# Clocl.net
KiCad netlist of a schematic drawn in Altium Designer
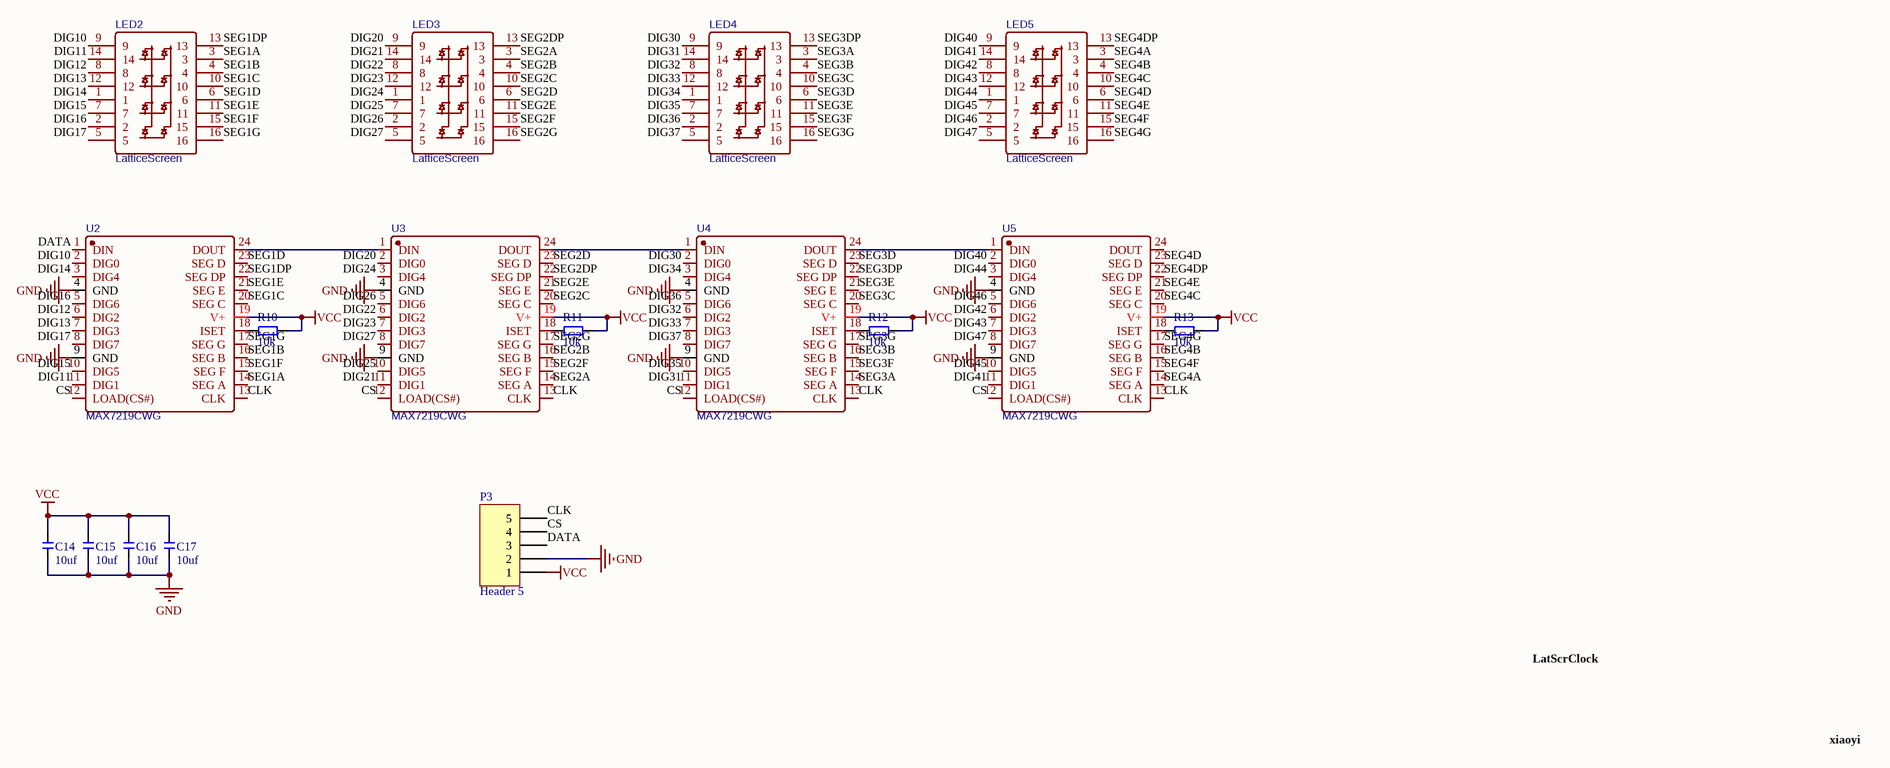
[diagram p0: Clocl.SchDoc]

(export (version "E")
  (design (tool "Eeschema 10.0.6"))
  (components
    (comp (ref "C14")
      (value "10uf")
      (footprint "C0805")
      (description "无极电容")
      (libsource (lib "SWJTUCar") (part "CAP"))
    )
    (comp (ref "C15")
      (value "10uf")
      (footprint "C0805")
      (description "无极电容")
      (libsource (lib "SWJTUCar") (part "CAP"))
    )
    (comp (ref "C16")
      (value "10uf")
      (footprint "C0805")
      (description "无极电容")
      (libsource (lib "SWJTUCar") (part "CAP"))
    )
    (comp (ref "C17")
      (value "10uf")
      (footprint "C0805")
      (description "无极电容")
      (libsource (lib "SWJTUCar") (part "CAP"))
    )
    (comp (ref "LED2")
      (value "LatticeScreen")
      (footprint "SLD1388DRA1GD_20_withheaders")
      (description "8*8共阴点阵屏")
      (fields
        (field (name "BOM_SUPPLIER PART") "C225991")
        (field (name "BOM_MANUFACTURER PART") "SLD1388DRA1GD")
        (field (name "CONTRIBUTOR") "LCSC")
      )
      (libsource (lib "myself") (part "LatticeScreen"))
    )
    (comp (ref "LED3")
      (value "LatticeScreen")
      (footprint "SLD1388DRA1GD_20_withheaders")
      (description "8*8共阴点阵屏")
      (fields
        (field (name "BOM_SUPPLIER PART") "C225991")
        (field (name "BOM_MANUFACTURER PART") "SLD1388DRA1GD")
        (field (name "CONTRIBUTOR") "LCSC")
      )
      (libsource (lib "myself") (part "LatticeScreen"))
    )
    (comp (ref "LED4")
      (value "LatticeScreen")
      (footprint "SLD1388DRA1GD_20_withheaders")
      (description "8*8共阴点阵屏")
      (fields
        (field (name "BOM_SUPPLIER PART") "C225991")
        (field (name "BOM_MANUFACTURER PART") "SLD1388DRA1GD")
        (field (name "CONTRIBUTOR") "LCSC")
      )
      (libsource (lib "myself") (part "LatticeScreen"))
    )
    (comp (ref "LED5")
      (value "LatticeScreen")
      (footprint "SLD1388DRA1GD_20_withheaders")
      (description "8*8共阴点阵屏")
      (fields
        (field (name "BOM_SUPPLIER PART") "C225991")
        (field (name "BOM_MANUFACTURER PART") "SLD1388DRA1GD")
        (field (name "CONTRIBUTOR") "LCSC")
      )
      (libsource (lib "myself") (part "LatticeScreen"))
    )
    (comp (ref "P3")
      (value "Header 5")
      (footprint "HDR1X5")
      (description "Header, 5-Pin")
      (fields (field (name "PUBLISHER") "Altium Limited"))
      (libsource (lib "Miscellaneous Connectors") (part "Header 5"))
    )
    (comp (ref "R10")
      (value "10k")
      (footprint "R0805")
      (description "电阻")
      (libsource (lib "SWJTUCar") (part "RES"))
    )
    (comp (ref "R11")
      (value "10k")
      (footprint "R0805")
      (description "电阻")
      (libsource (lib "SWJTUCar") (part "RES"))
    )
    (comp (ref "R12")
      (value "10k")
      (footprint "R0805")
      (description "电阻")
      (libsource (lib "SWJTUCar") (part "RES"))
    )
    (comp (ref "R13")
      (value "10k")
      (footprint "R0805")
      (description "电阻")
      (libsource (lib "SWJTUCar") (part "RES"))
    )
    (comp (ref "U2")
      (value "MAX7219CWG")
      (footprint "SOP-24_L15.2-W7.8-P1.27-LS10.6-BL")
      (description "共阴极显示驱动")
      (fields (field (name "BOM_SUPPLIER PART") "C9964"))
      (libsource (lib "myself") (part "MAX7219CWG"))
    )
    (comp (ref "U3")
      (value "MAX7219CWG")
      (footprint "SOP-24_L15.2-W7.8-P1.27-LS10.6-BL")
      (description "共阴极显示驱动")
      (fields (field (name "BOM_SUPPLIER PART") "C9964"))
      (libsource (lib "myself") (part "MAX7219CWG"))
    )
    (comp (ref "U4")
      (value "MAX7219CWG")
      (footprint "SOP-24_L15.2-W7.8-P1.27-LS10.6-BL")
      (description "共阴极显示驱动")
      (fields (field (name "BOM_SUPPLIER PART") "C9964"))
      (libsource (lib "myself") (part "MAX7219CWG"))
    )
    (comp (ref "U5")
      (value "MAX7219CWG")
      (footprint "SOP-24_L15.2-W7.8-P1.27-LS10.6-BL")
      (description "共阴极显示驱动")
      (fields (field (name "BOM_SUPPLIER PART") "C9964"))
      (libsource (lib "myself") (part "MAX7219CWG"))
    )
  )
  (nets
    (net (code "1") (name "/CLK") (class "Default")
      (node (ref "P3") (pin "5") (pinfunction "5_5") (pintype "passive"))
      (node (ref "U2") (pin "13") (pinfunction "CLK_13") (pintype "passive"))
      (node (ref "U3") (pin "13") (pinfunction "CLK_13") (pintype "passive"))
      (node (ref "U4") (pin "13") (pinfunction "CLK_13") (pintype "passive"))
      (node (ref "U5") (pin "13") (pinfunction "CLK_13") (pintype "passive"))
    )
    (net (code "2") (name "/CS") (class "Default")
      (node (ref "P3") (pin "4") (pinfunction "4_4") (pintype "passive"))
      (node (ref "U2") (pin "12") (pinfunction "LOAD(CS#)_12") (pintype "passive"))
      (node (ref "U3") (pin "12") (pinfunction "LOAD(CS#)_12") (pintype "passive"))
      (node (ref "U4") (pin "12") (pinfunction "LOAD(CS#)_12") (pintype "passive"))
      (node (ref "U5") (pin "12") (pinfunction "LOAD(CS#)_12") (pintype "passive"))
    )
    (net (code "3") (name "/DATA") (class "Default")
      (node (ref "P3") (pin "3") (pinfunction "3_3") (pintype "passive"))
      (node (ref "U2") (pin "1") (pinfunction "DIN_1") (pintype "passive"))
    )
    (net (code "4") (name "/DIG10") (class "Default")
      (node (ref "LED2") (pin "9") (pinfunction "9_9") (pintype "passive"))
      (node (ref "U2") (pin "2") (pinfunction "DIG0_2") (pintype "passive"))
    )
    (net (code "5") (name "/DIG11") (class "Default")
      (node (ref "LED2") (pin "14") (pinfunction "14_14") (pintype "passive"))
      (node (ref "U2") (pin "11") (pinfunction "DIG1_11") (pintype "passive"))
    )
    (net (code "6") (name "/DIG12") (class "Default")
      (node (ref "LED2") (pin "8") (pinfunction "8_8") (pintype "passive"))
      (node (ref "U2") (pin "6") (pinfunction "DIG2_6") (pintype "passive"))
    )
    (net (code "7") (name "/DIG13") (class "Default")
      (node (ref "LED2") (pin "12") (pinfunction "12_12") (pintype "passive"))
      (node (ref "U2") (pin "7") (pinfunction "DIG3_7") (pintype "passive"))
    )
    (net (code "8") (name "/DIG14") (class "Default")
      (node (ref "LED2") (pin "1") (pinfunction "1_1") (pintype "passive"))
      (node (ref "U2") (pin "3") (pinfunction "DIG4_3") (pintype "passive"))
    )
    (net (code "9") (name "/DIG15") (class "Default")
      (node (ref "LED2") (pin "7") (pinfunction "7_7") (pintype "passive"))
      (node (ref "U2") (pin "10") (pinfunction "DIG5_10") (pintype "passive"))
    )
    (net (code "10") (name "/DIG16") (class "Default")
      (node (ref "LED2") (pin "2") (pinfunction "2_2") (pintype "passive"))
      (node (ref "U2") (pin "5") (pinfunction "DIG6_5") (pintype "passive"))
    )
    (net (code "11") (name "/DIG17") (class "Default")
      (node (ref "LED2") (pin "5") (pinfunction "5_5") (pintype "passive"))
      (node (ref "U2") (pin "8") (pinfunction "DIG7_8") (pintype "passive"))
    )
    (net (code "12") (name "/DIG20") (class "Default")
      (node (ref "LED3") (pin "9") (pinfunction "9_9") (pintype "passive"))
      (node (ref "U3") (pin "2") (pinfunction "DIG0_2") (pintype "passive"))
    )
    (net (code "13") (name "/DIG21") (class "Default")
      (node (ref "LED3") (pin "14") (pinfunction "14_14") (pintype "passive"))
      (node (ref "U3") (pin "11") (pinfunction "DIG1_11") (pintype "passive"))
    )
    (net (code "14") (name "/DIG22") (class "Default")
      (node (ref "LED3") (pin "8") (pinfunction "8_8") (pintype "passive"))
      (node (ref "U3") (pin "6") (pinfunction "DIG2_6") (pintype "passive"))
    )
    (net (code "15") (name "/DIG23") (class "Default")
      (node (ref "LED3") (pin "12") (pinfunction "12_12") (pintype "passive"))
      (node (ref "U3") (pin "7") (pinfunction "DIG3_7") (pintype "passive"))
    )
    (net (code "16") (name "/DIG24") (class "Default")
      (node (ref "LED3") (pin "1") (pinfunction "1_1") (pintype "passive"))
      (node (ref "U3") (pin "3") (pinfunction "DIG4_3") (pintype "passive"))
    )
    (net (code "17") (name "/DIG25") (class "Default")
      (node (ref "LED3") (pin "7") (pinfunction "7_7") (pintype "passive"))
      (node (ref "U3") (pin "10") (pinfunction "DIG5_10") (pintype "passive"))
    )
    (net (code "18") (name "/DIG26") (class "Default")
      (node (ref "LED3") (pin "2") (pinfunction "2_2") (pintype "passive"))
      (node (ref "U3") (pin "5") (pinfunction "DIG6_5") (pintype "passive"))
    )
    (net (code "19") (name "/DIG27") (class "Default")
      (node (ref "LED3") (pin "5") (pinfunction "5_5") (pintype "passive"))
      (node (ref "U3") (pin "8") (pinfunction "DIG7_8") (pintype "passive"))
    )
    (net (code "20") (name "/DIG30") (class "Default")
      (node (ref "LED4") (pin "9") (pinfunction "9_9") (pintype "passive"))
      (node (ref "U4") (pin "2") (pinfunction "DIG0_2") (pintype "passive"))
    )
    (net (code "21") (name "/DIG31") (class "Default")
      (node (ref "LED4") (pin "14") (pinfunction "14_14") (pintype "passive"))
      (node (ref "U4") (pin "11") (pinfunction "DIG1_11") (pintype "passive"))
    )
    (net (code "22") (name "/DIG32") (class "Default")
      (node (ref "LED4") (pin "8") (pinfunction "8_8") (pintype "passive"))
      (node (ref "U4") (pin "6") (pinfunction "DIG2_6") (pintype "passive"))
    )
    (net (code "23") (name "/DIG33") (class "Default")
      (node (ref "LED4") (pin "12") (pinfunction "12_12") (pintype "passive"))
      (node (ref "U4") (pin "7") (pinfunction "DIG3_7") (pintype "passive"))
    )
    (net (code "24") (name "/DIG34") (class "Default")
      (node (ref "LED4") (pin "1") (pinfunction "1_1") (pintype "passive"))
      (node (ref "U4") (pin "3") (pinfunction "DIG4_3") (pintype "passive"))
    )
    (net (code "25") (name "/DIG35") (class "Default")
      (node (ref "LED4") (pin "7") (pinfunction "7_7") (pintype "passive"))
      (node (ref "U4") (pin "10") (pinfunction "DIG5_10") (pintype "passive"))
    )
    (net (code "26") (name "/DIG36") (class "Default")
      (node (ref "LED4") (pin "2") (pinfunction "2_2") (pintype "passive"))
      (node (ref "U4") (pin "5") (pinfunction "DIG6_5") (pintype "passive"))
    )
    (net (code "27") (name "/DIG37") (class "Default")
      (node (ref "LED4") (pin "5") (pinfunction "5_5") (pintype "passive"))
      (node (ref "U4") (pin "8") (pinfunction "DIG7_8") (pintype "passive"))
    )
    (net (code "28") (name "/DIG40") (class "Default")
      (node (ref "LED5") (pin "9") (pinfunction "9_9") (pintype "passive"))
      (node (ref "U5") (pin "2") (pinfunction "DIG0_2") (pintype "passive"))
    )
    (net (code "29") (name "/DIG41") (class "Default")
      (node (ref "LED5") (pin "14") (pinfunction "14_14") (pintype "passive"))
      (node (ref "U5") (pin "11") (pinfunction "DIG1_11") (pintype "passive"))
    )
    (net (code "30") (name "/DIG42") (class "Default")
      (node (ref "LED5") (pin "8") (pinfunction "8_8") (pintype "passive"))
      (node (ref "U5") (pin "6") (pinfunction "DIG2_6") (pintype "passive"))
    )
    (net (code "31") (name "/DIG43") (class "Default")
      (node (ref "LED5") (pin "12") (pinfunction "12_12") (pintype "passive"))
      (node (ref "U5") (pin "7") (pinfunction "DIG3_7") (pintype "passive"))
    )
    (net (code "32") (name "/DIG44") (class "Default")
      (node (ref "LED5") (pin "1") (pinfunction "1_1") (pintype "passive"))
      (node (ref "U5") (pin "3") (pinfunction "DIG4_3") (pintype "passive"))
    )
    (net (code "33") (name "/DIG45") (class "Default")
      (node (ref "LED5") (pin "7") (pinfunction "7_7") (pintype "passive"))
      (node (ref "U5") (pin "10") (pinfunction "DIG5_10") (pintype "passive"))
    )
    (net (code "34") (name "/DIG46") (class "Default")
      (node (ref "LED5") (pin "2") (pinfunction "2_2") (pintype "passive"))
      (node (ref "U5") (pin "5") (pinfunction "DIG6_5") (pintype "passive"))
    )
    (net (code "35") (name "/DIG47") (class "Default")
      (node (ref "LED5") (pin "5") (pinfunction "5_5") (pintype "passive"))
      (node (ref "U5") (pin "8") (pinfunction "DIG7_8") (pintype "passive"))
    )
    (net (code "36") (name "/SEG1A") (class "Default")
      (node (ref "LED2") (pin "3") (pinfunction "3_3") (pintype "passive"))
      (node (ref "U2") (pin "14") (pinfunction "SEG_A_14") (pintype "passive"))
    )
    (net (code "37") (name "/SEG1B") (class "Default")
      (node (ref "LED2") (pin "4") (pinfunction "4_4") (pintype "passive"))
      (node (ref "U2") (pin "16") (pinfunction "SEG_B_16") (pintype "passive"))
    )
    (net (code "38") (name "/SEG1C") (class "Default")
      (node (ref "LED2") (pin "10") (pinfunction "10_10") (pintype "passive"))
      (node (ref "U2") (pin "20") (pinfunction "SEG_C_20") (pintype "passive"))
    )
    (net (code "39") (name "/SEG1D") (class "Default")
      (node (ref "LED2") (pin "6") (pinfunction "6_6") (pintype "passive"))
      (node (ref "U2") (pin "23") (pinfunction "SEG_D_23") (pintype "passive"))
    )
    (net (code "40") (name "/SEG1DP") (class "Default")
      (node (ref "LED2") (pin "13") (pinfunction "13_13") (pintype "passive"))
      (node (ref "U2") (pin "22") (pinfunction "SEG_DP_22") (pintype "passive"))
    )
    (net (code "41") (name "/SEG1E") (class "Default")
      (node (ref "LED2") (pin "11") (pinfunction "11_11") (pintype "passive"))
      (node (ref "U2") (pin "21") (pinfunction "SEG_E_21") (pintype "passive"))
    )
    (net (code "42") (name "/SEG1F") (class "Default")
      (node (ref "LED2") (pin "15") (pinfunction "15_15") (pintype "passive"))
      (node (ref "U2") (pin "15") (pinfunction "SEG_F_15") (pintype "passive"))
    )
    (net (code "43") (name "/SEG1G") (class "Default")
      (node (ref "LED2") (pin "16") (pinfunction "16_16") (pintype "passive"))
      (node (ref "U2") (pin "17") (pinfunction "SEG_G_17") (pintype "passive"))
    )
    (net (code "44") (name "/SEG2A") (class "Default")
      (node (ref "LED3") (pin "3") (pinfunction "3_3") (pintype "passive"))
      (node (ref "U3") (pin "14") (pinfunction "SEG_A_14") (pintype "passive"))
    )
    (net (code "45") (name "/SEG2B") (class "Default")
      (node (ref "LED3") (pin "4") (pinfunction "4_4") (pintype "passive"))
      (node (ref "U3") (pin "16") (pinfunction "SEG_B_16") (pintype "passive"))
    )
    (net (code "46") (name "/SEG2C") (class "Default")
      (node (ref "LED3") (pin "10") (pinfunction "10_10") (pintype "passive"))
      (node (ref "U3") (pin "20") (pinfunction "SEG_C_20") (pintype "passive"))
    )
    (net (code "47") (name "/SEG2D") (class "Default")
      (node (ref "LED3") (pin "6") (pinfunction "6_6") (pintype "passive"))
      (node (ref "U3") (pin "23") (pinfunction "SEG_D_23") (pintype "passive"))
    )
    (net (code "48") (name "/SEG2DP") (class "Default")
      (node (ref "LED3") (pin "13") (pinfunction "13_13") (pintype "passive"))
      (node (ref "U3") (pin "22") (pinfunction "SEG_DP_22") (pintype "passive"))
    )
    (net (code "49") (name "/SEG2E") (class "Default")
      (node (ref "LED3") (pin "11") (pinfunction "11_11") (pintype "passive"))
      (node (ref "U3") (pin "21") (pinfunction "SEG_E_21") (pintype "passive"))
    )
    (net (code "50") (name "/SEG2F") (class "Default")
      (node (ref "LED3") (pin "15") (pinfunction "15_15") (pintype "passive"))
      (node (ref "U3") (pin "15") (pinfunction "SEG_F_15") (pintype "passive"))
    )
    (net (code "51") (name "/SEG2G") (class "Default")
      (node (ref "LED3") (pin "16") (pinfunction "16_16") (pintype "passive"))
      (node (ref "U3") (pin "17") (pinfunction "SEG_G_17") (pintype "passive"))
    )
    (net (code "52") (name "/SEG3A") (class "Default")
      (node (ref "LED4") (pin "3") (pinfunction "3_3") (pintype "passive"))
      (node (ref "U4") (pin "14") (pinfunction "SEG_A_14") (pintype "passive"))
    )
    (net (code "53") (name "/SEG3B") (class "Default")
      (node (ref "LED4") (pin "4") (pinfunction "4_4") (pintype "passive"))
      (node (ref "U4") (pin "16") (pinfunction "SEG_B_16") (pintype "passive"))
    )
    (net (code "54") (name "/SEG3C") (class "Default")
      (node (ref "LED4") (pin "10") (pinfunction "10_10") (pintype "passive"))
      (node (ref "U4") (pin "20") (pinfunction "SEG_C_20") (pintype "passive"))
    )
    (net (code "55") (name "/SEG3D") (class "Default")
      (node (ref "LED4") (pin "6") (pinfunction "6_6") (pintype "passive"))
      (node (ref "U4") (pin "23") (pinfunction "SEG_D_23") (pintype "passive"))
    )
    (net (code "56") (name "/SEG3DP") (class "Default")
      (node (ref "LED4") (pin "13") (pinfunction "13_13") (pintype "passive"))
      (node (ref "U4") (pin "22") (pinfunction "SEG_DP_22") (pintype "passive"))
    )
    (net (code "57") (name "/SEG3E") (class "Default")
      (node (ref "LED4") (pin "11") (pinfunction "11_11") (pintype "passive"))
      (node (ref "U4") (pin "21") (pinfunction "SEG_E_21") (pintype "passive"))
    )
    (net (code "58") (name "/SEG3F") (class "Default")
      (node (ref "LED4") (pin "15") (pinfunction "15_15") (pintype "passive"))
      (node (ref "U4") (pin "15") (pinfunction "SEG_F_15") (pintype "passive"))
    )
    (net (code "59") (name "/SEG3G") (class "Default")
      (node (ref "LED4") (pin "16") (pinfunction "16_16") (pintype "passive"))
      (node (ref "U4") (pin "17") (pinfunction "SEG_G_17") (pintype "passive"))
    )
    (net (code "60") (name "/SEG4A") (class "Default")
      (node (ref "LED5") (pin "3") (pinfunction "3_3") (pintype "passive"))
      (node (ref "U5") (pin "14") (pinfunction "SEG_A_14") (pintype "passive"))
    )
    (net (code "61") (name "/SEG4B") (class "Default")
      (node (ref "LED5") (pin "4") (pinfunction "4_4") (pintype "passive"))
      (node (ref "U5") (pin "16") (pinfunction "SEG_B_16") (pintype "passive"))
    )
    (net (code "62") (name "/SEG4C") (class "Default")
      (node (ref "LED5") (pin "10") (pinfunction "10_10") (pintype "passive"))
      (node (ref "U5") (pin "20") (pinfunction "SEG_C_20") (pintype "passive"))
    )
    (net (code "63") (name "/SEG4D") (class "Default")
      (node (ref "LED5") (pin "6") (pinfunction "6_6") (pintype "passive"))
      (node (ref "U5") (pin "23") (pinfunction "SEG_D_23") (pintype "passive"))
    )
    (net (code "64") (name "/SEG4DP") (class "Default")
      (node (ref "LED5") (pin "13") (pinfunction "13_13") (pintype "passive"))
      (node (ref "U5") (pin "22") (pinfunction "SEG_DP_22") (pintype "passive"))
    )
    (net (code "65") (name "/SEG4E") (class "Default")
      (node (ref "LED5") (pin "11") (pinfunction "11_11") (pintype "passive"))
      (node (ref "U5") (pin "21") (pinfunction "SEG_E_21") (pintype "passive"))
    )
    (net (code "66") (name "/SEG4F") (class "Default")
      (node (ref "LED5") (pin "15") (pinfunction "15_15") (pintype "passive"))
      (node (ref "U5") (pin "15") (pinfunction "SEG_F_15") (pintype "passive"))
    )
    (net (code "67") (name "/SEG4G") (class "Default")
      (node (ref "LED5") (pin "16") (pinfunction "16_16") (pintype "passive"))
      (node (ref "U5") (pin "17") (pinfunction "SEG_G_17") (pintype "passive"))
    )
    (net (code "68") (name "GND") (class "Default")
      (node (ref "C14") (pin "2") (pinfunction "2_2") (pintype "passive"))
      (node (ref "C15") (pin "2") (pinfunction "2_2") (pintype "passive"))
      (node (ref "C16") (pin "2") (pinfunction "2_2") (pintype "passive"))
      (node (ref "C17") (pin "2") (pinfunction "2_2") (pintype "passive"))
      (node (ref "P3") (pin "2") (pinfunction "2_2") (pintype "passive"))
      (node (ref "U2") (pin "4") (pinfunction "GND_4") (pintype "passive"))
      (node (ref "U2") (pin "9") (pinfunction "GND_9") (pintype "passive"))
      (node (ref "U3") (pin "4") (pinfunction "GND_4") (pintype "passive"))
      (node (ref "U3") (pin "9") (pinfunction "GND_9") (pintype "passive"))
      (node (ref "U4") (pin "4") (pinfunction "GND_4") (pintype "passive"))
      (node (ref "U4") (pin "9") (pinfunction "GND_9") (pintype "passive"))
      (node (ref "U5") (pin "4") (pinfunction "GND_4") (pintype "passive"))
      (node (ref "U5") (pin "9") (pinfunction "GND_9") (pintype "passive"))
    )
    (net (code "69") (name "Net-(U2-DOUT)") (class "Default")
      (node (ref "U2") (pin "24") (pinfunction "DOUT_24") (pintype "passive"))
      (node (ref "U3") (pin "1") (pinfunction "DIN_1") (pintype "passive"))
    )
    (net (code "70") (name "Net-(U2-ISET)") (class "Default")
      (node (ref "R10") (pin "2") (pinfunction "2_2") (pintype "passive"))
      (node (ref "U2") (pin "18") (pinfunction "ISET_18") (pintype "passive"))
    )
    (net (code "71") (name "Net-(U3-DOUT)") (class "Default")
      (node (ref "U3") (pin "24") (pinfunction "DOUT_24") (pintype "passive"))
      (node (ref "U4") (pin "1") (pinfunction "DIN_1") (pintype "passive"))
    )
    (net (code "72") (name "Net-(U3-ISET)") (class "Default")
      (node (ref "R11") (pin "2") (pinfunction "2_2") (pintype "passive"))
      (node (ref "U3") (pin "18") (pinfunction "ISET_18") (pintype "passive"))
    )
    (net (code "73") (name "Net-(U4-DOUT)") (class "Default")
      (node (ref "U4") (pin "24") (pinfunction "DOUT_24") (pintype "passive"))
      (node (ref "U5") (pin "1") (pinfunction "DIN_1") (pintype "passive"))
    )
    (net (code "74") (name "Net-(U4-ISET)") (class "Default")
      (node (ref "R12") (pin "2") (pinfunction "2_2") (pintype "passive"))
      (node (ref "U4") (pin "18") (pinfunction "ISET_18") (pintype "passive"))
    )
    (net (code "75") (name "Net-(U5-ISET)") (class "Default")
      (node (ref "R13") (pin "2") (pinfunction "2_2") (pintype "passive"))
      (node (ref "U5") (pin "18") (pinfunction "ISET_18") (pintype "passive"))
    )
    (net (code "76") (name "VCC") (class "Default")
      (node (ref "C14") (pin "1") (pinfunction "1_1") (pintype "passive"))
      (node (ref "C15") (pin "1") (pinfunction "1_1") (pintype "passive"))
      (node (ref "C16") (pin "1") (pinfunction "1_1") (pintype "passive"))
      (node (ref "C17") (pin "1") (pinfunction "1_1") (pintype "passive"))
      (node (ref "P3") (pin "1") (pinfunction "1_1") (pintype "passive"))
      (node (ref "R10") (pin "1") (pinfunction "1_1") (pintype "passive"))
      (node (ref "R11") (pin "1") (pinfunction "1_1") (pintype "passive"))
      (node (ref "R12") (pin "1") (pinfunction "1_1") (pintype "passive"))
      (node (ref "R13") (pin "1") (pinfunction "1_1") (pintype "passive"))
      (node (ref "U2") (pin "19") (pinfunction "V+_19") (pintype "passive"))
      (node (ref "U3") (pin "19") (pinfunction "V+_19") (pintype "passive"))
      (node (ref "U4") (pin "19") (pinfunction "V+_19") (pintype "passive"))
      (node (ref "U5") (pin "19") (pinfunction "V+_19") (pintype "passive"))
    )
    (net (code "77") (name "unconnected-(U5-DOUT-Pad24)") (class "Default")
      (node (ref "U5") (pin "24") (pinfunction "DOUT_24") (pintype "passive"))
    )
  )
)
